# Solens.net
KiCad netlist of a schematic drawn in Altium Designer
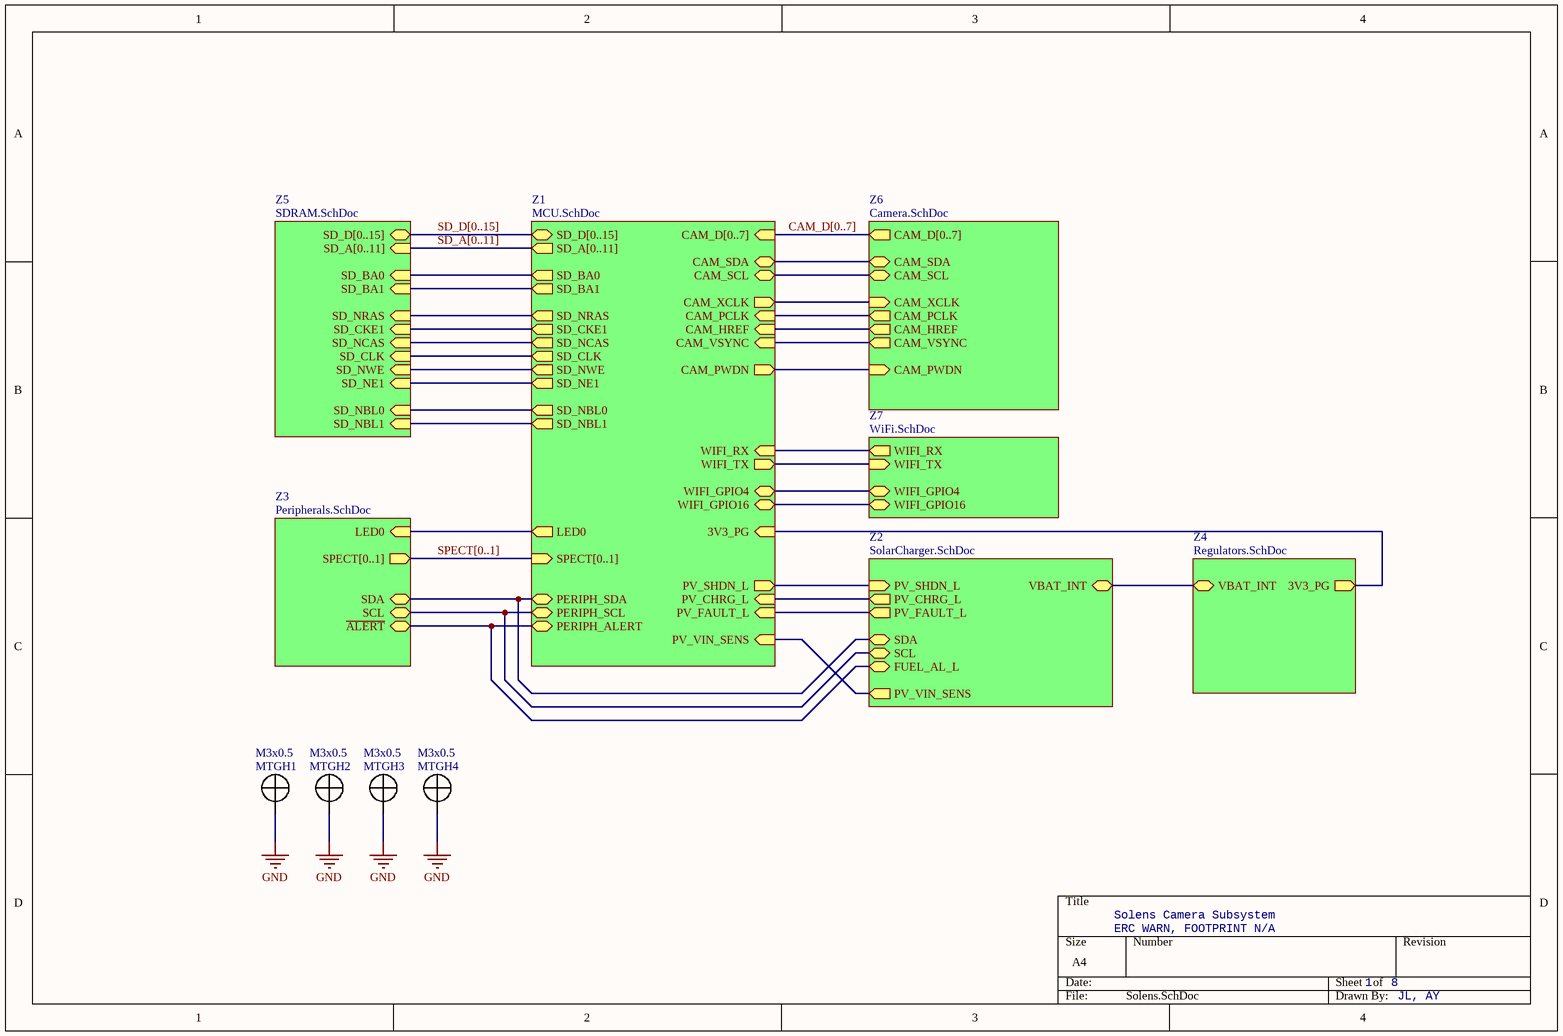
[diagram p0: Solens.SchDoc]

(export (version "E")
  (design (tool "Eeschema 10.0.6"))
  (components
    (comp (ref "MTGH1")
      (value "M3x0.5 (DNP)")
      (footprint "MTGH-M3x0.5-ClipSW")
      (description "Mounting hole")
      (fields (field (name "SCREWSIZE") "M3x0.5"))
      (libsource (lib "Schlib1") (part "MTGH"))
    )
    (comp (ref "MTGH2")
      (value "M3x0.5 (DNP)")
      (footprint "MTGH-M3x0.5-ClipNW")
      (description "Mounting hole")
      (fields (field (name "SCREWSIZE") "M3x0.5"))
      (libsource (lib "Schlib1") (part "MTGH"))
    )
    (comp (ref "MTGH3")
      (value "M3x0.5 (DNP)")
      (footprint "MTGH-M3x0.5-ClipNE")
      (description "Mounting hole")
      (fields (field (name "SCREWSIZE") "M3x0.5"))
      (libsource (lib "Schlib1") (part "MTGH"))
    )
    (comp (ref "MTGH4")
      (value "M3x0.5 (DNP)")
      (footprint "MTGH-M3x0.5")
      (description "Mounting hole")
      (fields (field (name "SCREWSIZE") "M3x0.5"))
      (libsource (lib "Schlib1") (part "MTGH"))
    )
  )
  (nets
    (net (code "74") (name "GND") (class "Default")
      (node (ref "MTGH1") (pin "1") (pinfunction "1_1") (pintype "power_in"))
      (node (ref "MTGH2") (pin "1") (pinfunction "1_1") (pintype "power_in"))
      (node (ref "MTGH3") (pin "1") (pinfunction "1_1") (pintype "power_in"))
      (node (ref "MTGH4") (pin "1") (pinfunction "1_1") (pintype "power_in"))
    )
  )
)
